# imu_69.net
KiCad netlist of a schematic drawn in EAGLE
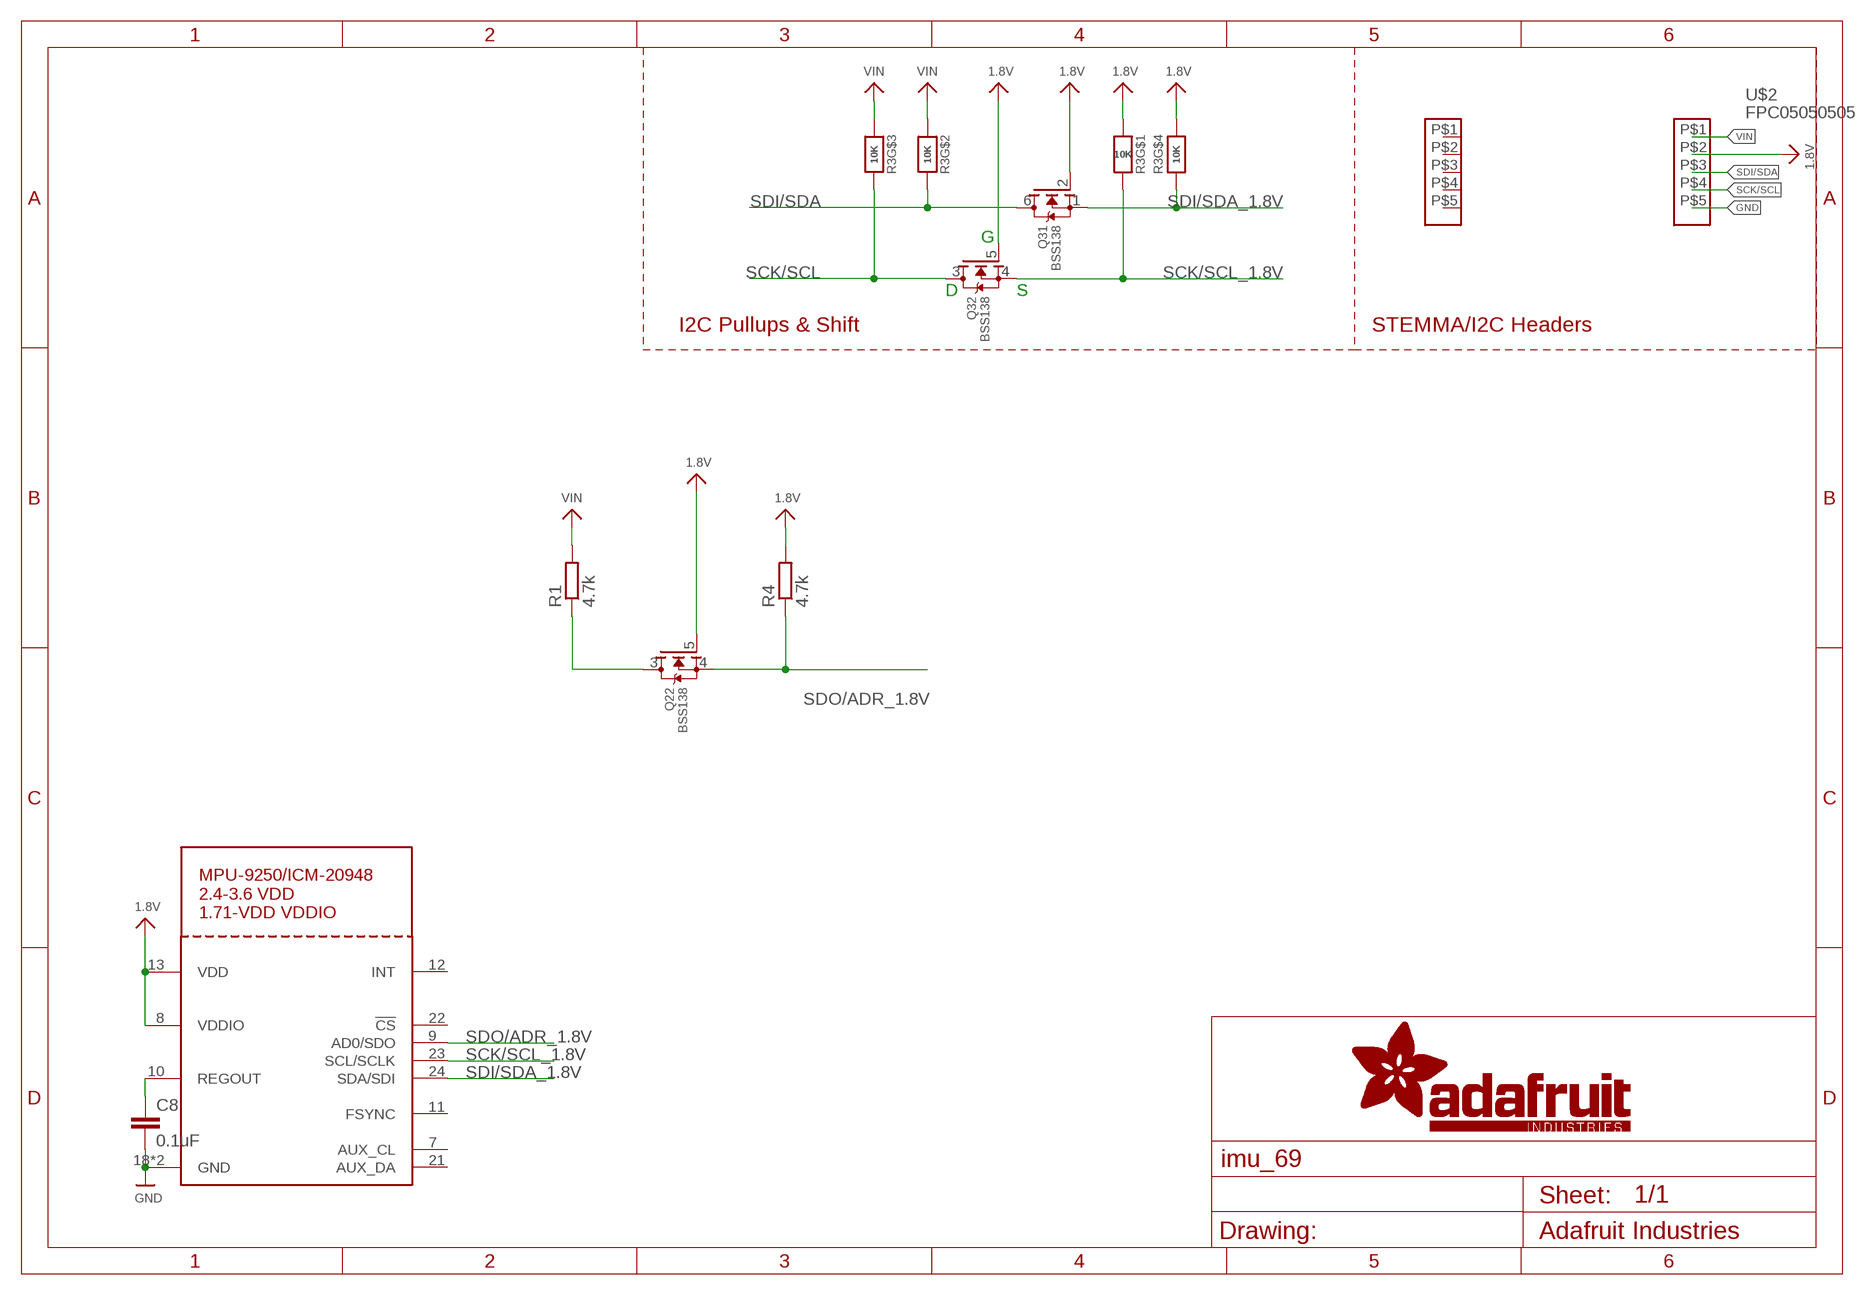
[diagram p0: schematic, sheet 1]

(export (version "E")
  (design (tool "Eeschema 10.0.6"))
  (components
    (comp (ref "C8")
      (value "0.1uF")
      (footprint "eagle-import:C0201")
      (libsource (lib "eagle-import") (part "C-EUC0201"))
    )
    (comp (ref "Q2")
      (value "BSS138")
      (footprint "eagle-import:SOT363")
      (libsource (lib "eagle-import") (part "MOSFET-N_DUAL"))
    )
    (comp (ref "Q3")
      (value "BSS138")
      (footprint "eagle-import:SOT363")
      (libsource (lib "eagle-import") (part "MOSFET-N_DUAL"))
    )
    (comp (ref "R1")
      (value "4.7k")
      (footprint "eagle-import:R0402")
      (libsource (lib "eagle-import") (part "R-EU_R0402"))
    )
    (comp (ref "R3")
      (value "10K")
      (footprint "eagle-import:RESPACK_4X0603")
      (libsource (lib "eagle-import") (part "RESISTOR_4PACK"))
    )
    (comp (ref "R4")
      (value "4.7k")
      (footprint "eagle-import:R0402")
      (libsource (lib "eagle-import") (part "R-EU_R0402"))
    )
    (comp (ref "U$1")
      (value "FPC05050505")
      (footprint "eagle-import:FPB0505")
      (libsource (lib "eagle-import") (part "FPC05050505"))
    )
    (comp (ref "U$2")
      (value "FPC05050505")
      (footprint "eagle-import:FPB0505")
      (libsource (lib "eagle-import") (part "FPC05050505"))
    )
    (comp (ref "U$21")
      (value "MPU-9250_ICM20948")
      (footprint "eagle-import:QFN24_3MM_NOEP")
      (libsource (lib "eagle-import") (part "MPU-9250_ICM20948"))
    )
  )
  (nets
    (net (code "1") (name "/SCK{slash}SCL_1.8V") (class "Default")
      (node (ref "Q3") (pin "4") (pinfunction "S_4") (pintype "bidirectional"))
      (node (ref "R3") (pin "1") (pinfunction "1_1") (pintype "passive"))
      (node (ref "U$21") (pin "23") (pinfunction "SCL/SCLK_23") (pintype "bidirectional"))
    )
    (net (code "2") (name "/SDI{slash}SDA_1.8V") (class "Default")
      (node (ref "Q3") (pin "1") (pinfunction "S_1") (pintype "bidirectional"))
      (node (ref "R3") (pin "5") (pinfunction "2_5") (pintype "passive"))
      (node (ref "U$21") (pin "24") (pinfunction "SDA/SDI_24") (pintype "bidirectional"))
    )
    (net (code "3") (name "/SDO{slash}ADR_1.8V") (class "Default")
      (node (ref "Q2") (pin "4") (pinfunction "S_4") (pintype "bidirectional"))
      (node (ref "R4") (pin "1") (pinfunction "1_1") (pintype "passive"))
      (node (ref "U$21") (pin "9") (pinfunction "AD0/SDO_9") (pintype "bidirectional"))
    )
    (net (code "4") (name "1.8V") (class "Default")
      (node (ref "Q2") (pin "5") (pinfunction "G_5") (pintype "bidirectional"))
      (node (ref "Q3") (pin "2") (pinfunction "G_2") (pintype "bidirectional"))
      (node (ref "Q3") (pin "5") (pinfunction "G_5") (pintype "bidirectional"))
      (node (ref "R3") (pin "4") (pinfunction "1_4") (pintype "passive"))
      (node (ref "R3") (pin "8") (pinfunction "2_8") (pintype "passive"))
      (node (ref "R4") (pin "2") (pinfunction "2_2") (pintype "passive"))
      (node (ref "U$2") (pin "P$2") (pinfunction "P$2_P$2") (pintype "bidirectional"))
      (node (ref "U$21") (pin "13") (pinfunction "VDD_13") (pintype "bidirectional"))
      (node (ref "U$21") (pin "8") (pinfunction "VDDIO_8") (pintype "bidirectional"))
    )
    (net (code "5") (name "GND") (class "Default")
      (node (ref "C8") (pin "2") (pinfunction "2_2") (pintype "passive"))
      (node (ref "U$2") (pin "P$5") (pinfunction "P$5_P$5") (pintype "bidirectional"))
      (node (ref "U$21") (pin "18") (pinfunction "GND_18") (pintype "bidirectional"))
      (node (ref "U$21") (pin "20") (pinfunction "GND_20") (pintype "bidirectional"))
    )
    (net (code "6") (name "Net-(Q2B-D)") (class "Default")
      (node (ref "Q2") (pin "3") (pinfunction "D_3") (pintype "bidirectional"))
      (node (ref "R1") (pin "1") (pinfunction "1_1") (pintype "passive"))
    )
    (net (code "7") (name "Net-(U$21-REGOUT)") (class "Default")
      (node (ref "C8") (pin "1") (pinfunction "1_1") (pintype "passive"))
      (node (ref "U$21") (pin "10") (pinfunction "REGOUT_10") (pintype "bidirectional"))
    )
    (net (code "8") (name "SCK{slash}SCL") (class "Default")
      (node (ref "Q3") (pin "3") (pinfunction "D_3") (pintype "bidirectional"))
      (node (ref "R3") (pin "6") (pinfunction "2_6") (pintype "passive"))
      (node (ref "U$2") (pin "P$4") (pinfunction "P$4_P$4") (pintype "bidirectional"))
    )
    (net (code "9") (name "SDI{slash}SDA") (class "Default")
      (node (ref "Q3") (pin "6") (pinfunction "D_6") (pintype "bidirectional"))
      (node (ref "R3") (pin "7") (pinfunction "2_7") (pintype "passive"))
      (node (ref "U$2") (pin "P$3") (pinfunction "P$3_P$3") (pintype "bidirectional"))
    )
    (net (code "10") (name "VIN") (class "Default")
      (node (ref "R1") (pin "2") (pinfunction "2_2") (pintype "passive"))
      (node (ref "R3") (pin "2") (pinfunction "1_2") (pintype "passive"))
      (node (ref "R3") (pin "3") (pinfunction "1_3") (pintype "passive"))
      (node (ref "U$2") (pin "P$1") (pinfunction "P$1_P$1") (pintype "bidirectional"))
    )
    (net (code "11") (name "unconnected-(U$1-PadP$1)") (class "Default")
      (node (ref "U$1") (pin "P$1") (pinfunction "P$1_P$1") (pintype "bidirectional"))
    )
    (net (code "12") (name "unconnected-(U$1-PadP$2)") (class "Default")
      (node (ref "U$1") (pin "P$2") (pinfunction "P$2_P$2") (pintype "bidirectional"))
    )
    (net (code "13") (name "unconnected-(U$1-PadP$3)") (class "Default")
      (node (ref "U$1") (pin "P$3") (pinfunction "P$3_P$3") (pintype "bidirectional"))
    )
    (net (code "14") (name "unconnected-(U$1-PadP$4)") (class "Default")
      (node (ref "U$1") (pin "P$4") (pinfunction "P$4_P$4") (pintype "bidirectional"))
    )
    (net (code "15") (name "unconnected-(U$1-PadP$5)") (class "Default")
      (node (ref "U$1") (pin "P$5") (pinfunction "P$5_P$5") (pintype "bidirectional"))
    )
    (net (code "16") (name "unconnected-(U$21-AUX_CL-Pad7)") (class "Default")
      (node (ref "U$21") (pin "7") (pinfunction "AUX_CL_7") (pintype "bidirectional"))
    )
    (net (code "17") (name "unconnected-(U$21-AUX_DA-Pad21)") (class "Default")
      (node (ref "U$21") (pin "21") (pinfunction "AUX_DA_21") (pintype "bidirectional"))
    )
    (net (code "18") (name "unconnected-(U$21-FSYNC-Pad11)") (class "Default")
      (node (ref "U$21") (pin "11") (pinfunction "FSYNC_11") (pintype "bidirectional"))
    )
    (net (code "19") (name "unconnected-(U$21-INT-Pad12)") (class "Default")
      (node (ref "U$21") (pin "12") (pinfunction "INT_12") (pintype "bidirectional"))
    )
    (net (code "20") (name "unconnected-(U$21-~{CS}-Pad22)") (class "Default")
      (node (ref "U$21") (pin "22") (pinfunction "~{CS}_22") (pintype "bidirectional"))
    )
  )
)
